# Power15V0_1A.net
KiCad netlist of a schematic drawn in Altium Designer
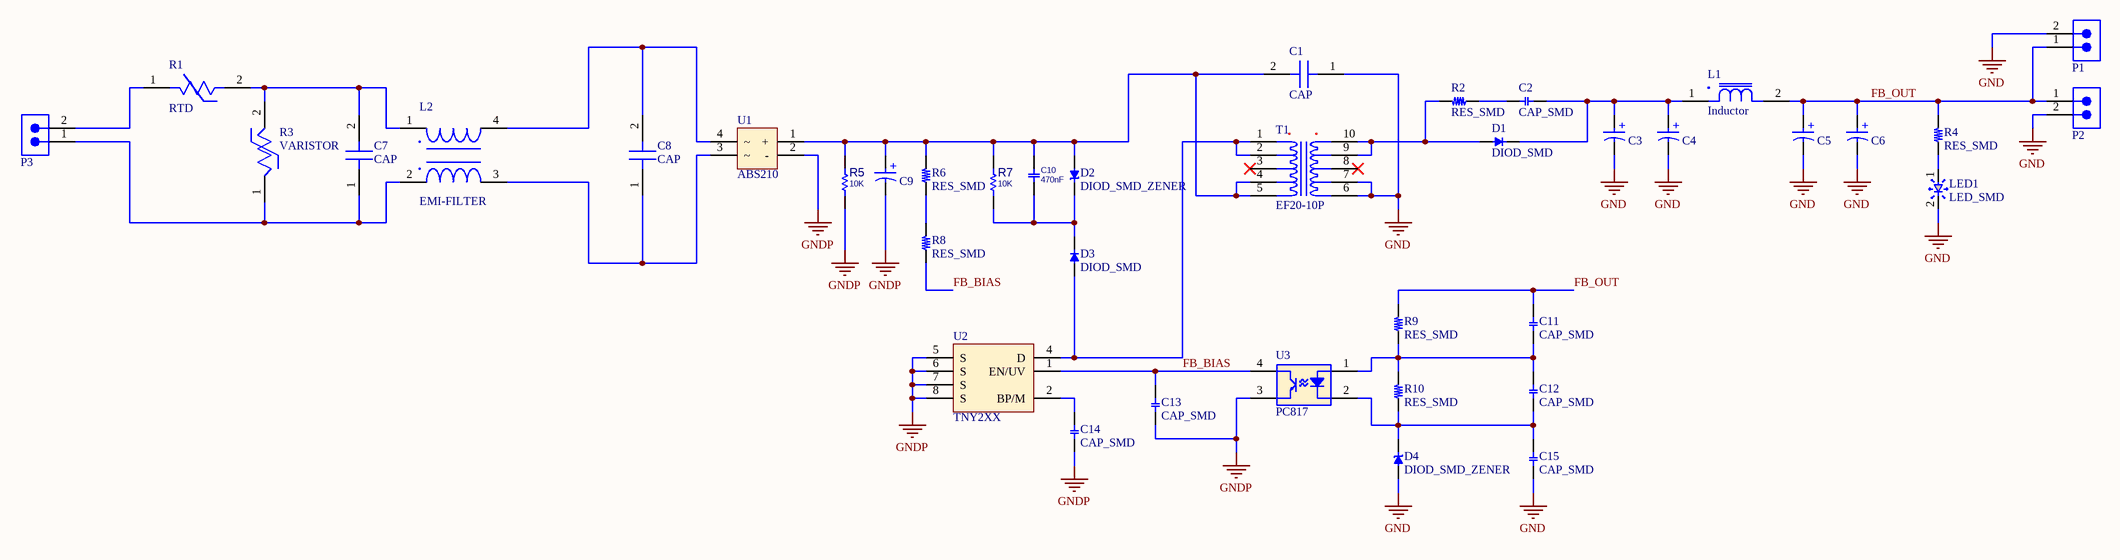
[diagram p0: Power15V0_1A.SchDoc]

(export (version "E")
  (design (tool "Eeschema 10.0.6"))
  (components
    (comp (ref "C1") (value "CAP") (footprint "CXY") (libsource (lib "radmehr_library") (part "CAP")))
    (comp (ref "C2")
      (value "CAP_SMD")
      (footprint "C 1206")
      (libsource (lib "radmehr_library") (part "CAP_SMD"))
    )
    (comp (ref "C3")
      (value "100µF")
      (footprint "WCAP-AS5H_D10H10.5")
      (description "WCAP-AS5H Aluminum Electrolytic Capacitor, V-Chip, D10 x H10.5mm, 100µF, 50V")
      (fields
        (field (name "MANUFACTURER PART NUMBER") "865230657013")
        (field (name "MANUFACTURER") "Wurth Elektronik")
      )
      (libsource (lib "Altium_WCAP-AS5H (rev22c)") (part "865230657013"))
    )
    (comp (ref "C4")
      (value "100µF")
      (footprint "WCAP-AS5H_D10H10.5")
      (description "WCAP-AS5H Aluminum Electrolytic Capacitor, V-Chip, D10 x H10.5mm, 100µF, 50V")
      (fields
        (field (name "MANUFACTURER PART NUMBER") "865230657013")
        (field (name "MANUFACTURER") "Wurth Elektronik")
      )
      (libsource (lib "Altium_WCAP-AS5H (rev22c)") (part "865230657013"))
    )
    (comp (ref "C5")
      (value "100µF")
      (footprint "WCAP-AS5H_D10H10.5")
      (description "WCAP-AS5H Aluminum Electrolytic Capacitor, V-Chip, D10 x H10.5mm, 100µF, 50V")
      (fields
        (field (name "MANUFACTURER PART NUMBER") "865230657013")
        (field (name "MANUFACTURER") "Wurth Elektronik")
      )
      (libsource (lib "Altium_WCAP-AS5H (rev22c)") (part "865230657013"))
    )
    (comp (ref "C6")
      (value "100µF")
      (footprint "WCAP-AS5H_D10H10.5")
      (description "WCAP-AS5H Aluminum Electrolytic Capacitor, V-Chip, D10 x H10.5mm, 100µF, 50V")
      (fields
        (field (name "MANUFACTURER PART NUMBER") "865230657013")
        (field (name "MANUFACTURER") "Wurth Elektronik")
      )
      (libsource (lib "Altium_WCAP-AS5H (rev22c)") (part "865230657013"))
    )
    (comp (ref "C7") (value "CAP") (footprint "CXY") (libsource (lib "radmehr_library") (part "CAP")))
    (comp (ref "C8") (value "CAP") (footprint "CXY") (libsource (lib "radmehr_library") (part "CAP")))
    (comp (ref "C9")
      (value "47µF")
      (footprint "WCAP-AIG8_D22H26")
      (description "WCAP-AIG8 Aluminum Electrolytic Capacitor, Snap-In, D22 x H26mm, 47µF, 450V")
      (fields
        (field (name "MANUFACTURER PART NUMBER") "861011483001")
        (field (name "MANUFACTURER") "Wurth Elektronik")
      )
      (libsource (lib "Altium_WCAP-AIG8 (rev22c)") (part "861011483001"))
    )
    (comp (ref "C10")
      (value "470nF")
      (footprint "C_PLY_6X3")
      (description "CAP, FILM,")
      (fields (field (name "MANF_P#") "MANF_PART#") (field (name "MANF") "MANF"))
      (libsource (lib "Integrated_Library_chilla") (part "CAP_THD_FILM_POLYESTER"))
    )
    (comp (ref "C11")
      (value "CAP_SMD")
      (footprint "C 1206")
      (libsource (lib "radmehr_library") (part "CAP_SMD"))
    )
    (comp (ref "C12")
      (value "CAP_SMD")
      (footprint "C 1206")
      (libsource (lib "radmehr_library") (part "CAP_SMD"))
    )
    (comp (ref "C13")
      (value "CAP_SMD")
      (footprint "C 1206")
      (libsource (lib "radmehr_library") (part "CAP_SMD"))
    )
    (comp (ref "C14")
      (value "CAP_SMD")
      (footprint "C 1206")
      (libsource (lib "radmehr_library") (part "CAP_SMD"))
    )
    (comp (ref "C15")
      (value "CAP_SMD")
      (footprint "C 1206")
      (libsource (lib "radmehr_library") (part "CAP_SMD"))
    )
    (comp (ref "D1")
      (value "DIOD_SMD")
      (footprint "DIOD_SMC")
      (libsource (lib "radmehr_library") (part "DIOD_SMD"))
    )
    (comp (ref "D2")
      (value "DIOD_SMD_ZENER")
      (footprint "DIOD_SMB")
      (libsource (lib "radmehr_library") (part "DIOD_SMD_ZENER"))
    )
    (comp (ref "D3")
      (value "DIOD_SMD")
      (footprint "DIOD_SMB")
      (libsource (lib "radmehr_library") (part "DIOD_SMD"))
    )
    (comp (ref "D4")
      (value "DIOD_SMD_ZENER")
      (footprint "DIOD_SMA")
      (libsource (lib "radmehr_library") (part "DIOD_SMD_ZENER"))
    )
    (comp (ref "L1")
      (value "Inductor")
      (footprint "L_12*12_SMD")
      (libsource (lib "radmehr_library") (part "Inductor"))
    )
    (comp (ref "L2")
      (value "EMI-FILTER")
      (footprint "EMI-FILTER-10*13")
      (libsource (lib "radmehr_library") (part "EMI-FILTER"))
    )
    (comp (ref "LED1")
      (value "LED_SMD")
      (footprint "D 1206")
      (libsource (lib "radmehr_library") (part "LED_SMD"))
    )
    (comp (ref "P1")
      (value "691322310002")
      (footprint "691322310002")
      (description "WR-TBL Series 322 Horizontal PCB Header, Through Hole, pitch 3.81mm, 2p")
      (fields (field (name "MANUFACTURER") "Wurth Elektronik"))
      (libsource (lib "Altium_WR-TBL (rev22a)") (part "691322310002"))
    )
    (comp (ref "P2")
      (value "691322310002")
      (footprint "691322310002")
      (description "WR-TBL Series 322 Horizontal PCB Header, Through Hole, pitch 3.81mm, 2p")
      (fields (field (name "MANUFACTURER") "Wurth Elektronik"))
      (libsource (lib "Altium_WR-TBL (rev22a)") (part "691322310002"))
    )
    (comp (ref "P3")
      (value "691322310002")
      (footprint "691322310002")
      (description "WR-TBL Series 322 Horizontal PCB Header, Through Hole, pitch 3.81mm, 2p")
      (fields (field (name "MANUFACTURER") "Wurth Elektronik"))
      (libsource (lib "Altium_WR-TBL (rev22a)") (part "691322310002"))
    )
    (comp (ref "R1") (value "RTD") (footprint "RTD") (libsource (lib "radmehr_library") (part "RTD")))
    (comp (ref "R2")
      (value "RES_SMD")
      (footprint "R 1206")
      (libsource (lib "radmehr_library") (part "RES_SMD"))
    )
    (comp (ref "R3")
      (value "VARISTOR")
      (footprint "RTD")
      (libsource (lib "radmehr_library") (part "VARISTOR"))
    )
    (comp (ref "R4")
      (value "RES_SMD")
      (footprint "R 1206")
      (libsource (lib "radmehr_library") (part "RES_SMD"))
    )
    (comp (ref "R5")
      (value "10K")
      (footprint "R025W_AX04")
      (description "RESISTOR, THD")
      (fields (field (name "MANF_P#") "RK73H1ETTP4701F") (field (name "MANF") "KOA SPEER"))
      (libsource (lib "Integrated_Library_chilla") (part "RES_THD"))
    )
    (comp (ref "R6")
      (value "RES_SMD")
      (footprint "R 1206")
      (libsource (lib "radmehr_library") (part "RES_SMD"))
    )
    (comp (ref "R7")
      (value "10K")
      (footprint "R2W_AX_VER")
      (description "RESISTOR, THD")
      (fields (field (name "MANF_P#") "RK73H1ETTP4701F") (field (name "MANF") "KOA SPEER"))
      (libsource (lib "Integrated_Library_chilla") (part "RES_THD"))
    )
    (comp (ref "R8")
      (value "RES_SMD")
      (footprint "R 1206")
      (libsource (lib "radmehr_library") (part "RES_SMD"))
    )
    (comp (ref "R9")
      (value "RES_SMD")
      (footprint "R 1206")
      (libsource (lib "radmehr_library") (part "RES_SMD"))
    )
    (comp (ref "R10")
      (value "RES_SMD")
      (footprint "R 1206")
      (libsource (lib "radmehr_library") (part "RES_SMD"))
    )
    (comp (ref "T1")
      (value "EF20-10P")
      (footprint "EF20-10P")
      (libsource (lib "radmehr_library") (part "EF20-10P"))
    )
    (comp (ref "U1") (value "ABS210") (footprint "ABS-4") (libsource (lib "radmehr_library") (part "ABS210")))
    (comp (ref "U2")
      (value "TNY2XX")
      (footprint "PDIP-8C")
      (description "P Package (DIP-8C)\r\nG Package (SMD-8C)")
      (libsource (lib "radmehr_library") (part "TNY2XX"))
    )
    (comp (ref "U3") (value "PC817") (footprint "PSMD-4") (libsource (lib "radmehr_library") (part "PC817")))
  )
  (nets
    (net (code "1") (name "/FB_BIAS") (class "Default")
      (node (ref "C13") (pin "2") (pinfunction "2_2") (pintype "passive"))
      (node (ref "R8") (pin "1") (pinfunction "1_1") (pintype "passive"))
      (node (ref "U2") (pin "1") (pinfunction "EN/UV_1") (pintype "power_in"))
      (node (ref "U3") (pin "4") (pinfunction "C_4") (pintype "passive"))
    )
    (net (code "2") (name "/FB_OUT") (class "Default")
      (node (ref "C11") (pin "1") (pinfunction "1_1") (pintype "passive"))
      (node (ref "C5") (pin "1") (pinfunction "P_1") (pintype "passive"))
      (node (ref "C6") (pin "1") (pinfunction "P_1") (pintype "passive"))
      (node (ref "L1") (pin "2") (pintype "passive"))
      (node (ref "P1") (pin "1") (pinfunction "1_1") (pintype "passive"))
      (node (ref "P2") (pin "1") (pinfunction "1_1") (pintype "passive"))
      (node (ref "R4") (pin "2") (pinfunction "2_2") (pintype "passive"))
      (node (ref "R9") (pin "2") (pinfunction "2_2") (pintype "passive"))
    )
    (net (code "3") (name "GND") (class "Default")
      (node (ref "C1") (pin "1") (pintype "passive"))
      (node (ref "C15") (pin "2") (pinfunction "2_2") (pintype "passive"))
      (node (ref "C3") (pin "2") (pinfunction "N_2") (pintype "passive"))
      (node (ref "C4") (pin "2") (pinfunction "N_2") (pintype "passive"))
      (node (ref "C5") (pin "2") (pinfunction "N_2") (pintype "passive"))
      (node (ref "C6") (pin "2") (pinfunction "N_2") (pintype "passive"))
      (node (ref "D4") (pin "1") (pinfunction "1_1") (pintype "passive"))
      (node (ref "LED1") (pin "2") (pintype "passive"))
      (node (ref "P1") (pin "2") (pinfunction "2_2") (pintype "passive"))
      (node (ref "P2") (pin "2") (pinfunction "2_2") (pintype "passive"))
      (node (ref "T1") (pin "6") (pinfunction "6_6") (pintype "power_in"))
      (node (ref "T1") (pin "7") (pinfunction "7_7") (pintype "power_in"))
    )
    (net (code "4") (name "GNDP") (class "Default")
      (node (ref "C13") (pin "1") (pinfunction "1_1") (pintype "passive"))
      (node (ref "C14") (pin "1") (pinfunction "1_1") (pintype "passive"))
      (node (ref "C9") (pin "2") (pinfunction "N_2") (pintype "passive"))
      (node (ref "R5") (pin "1") (pinfunction "1_1") (pintype "passive"))
      (node (ref "U1") (pin "2") (pinfunction "-_2") (pintype "power_in"))
      (node (ref "U2") (pin "5") (pinfunction "S_5") (pintype "power_in"))
      (node (ref "U2") (pin "6") (pinfunction "S_6") (pintype "power_in"))
      (node (ref "U2") (pin "7") (pinfunction "S_7") (pintype "power_in"))
      (node (ref "U2") (pin "8") (pinfunction "S_8") (pintype "power_in"))
      (node (ref "U3") (pin "3") (pinfunction "E_3") (pintype "passive"))
    )
    (net (code "5") (name "Net-(C2-Pad2)") (class "Default")
      (node (ref "C2") (pin "2") (pinfunction "2_2") (pintype "passive"))
      (node (ref "R2") (pin "1") (pinfunction "1_1") (pintype "passive"))
    )
    (net (code "6") (name "Net-(C3-P)") (class "Default")
      (node (ref "C2") (pin "1") (pinfunction "1_1") (pintype "passive"))
      (node (ref "C3") (pin "1") (pinfunction "P_1") (pintype "passive"))
      (node (ref "C4") (pin "1") (pinfunction "P_1") (pintype "passive"))
      (node (ref "D1") (pin "2") (pinfunction "2_2") (pintype "passive"))
      (node (ref "L1") (pin "1") (pintype "passive"))
    )
    (net (code "7") (name "Net-(C7-Pad1)") (class "Default")
      (node (ref "C7") (pin "1") (pintype "passive"))
      (node (ref "L2") (pin "2") (pinfunction "2_2") (pintype "power_in"))
      (node (ref "P3") (pin "1") (pinfunction "1_1") (pintype "passive"))
      (node (ref "R3") (pin "1") (pinfunction "1_1") (pintype "power_in"))
    )
    (net (code "8") (name "Net-(C7-Pad2)") (class "Default")
      (node (ref "C7") (pin "2") (pintype "passive"))
      (node (ref "L2") (pin "1") (pinfunction "1_1") (pintype "power_in"))
      (node (ref "R1") (pin "2") (pinfunction "2_2") (pintype "power_in"))
      (node (ref "R3") (pin "2") (pinfunction "2_2") (pintype "power_in"))
    )
    (net (code "9") (name "Net-(C8-Pad1)") (class "Default")
      (node (ref "C8") (pin "1") (pintype "passive"))
      (node (ref "L2") (pin "3") (pinfunction "3_3") (pintype "power_in"))
      (node (ref "U1") (pin "3") (pinfunction "~_3") (pintype "power_in"))
    )
    (net (code "10") (name "Net-(C8-Pad2)") (class "Default")
      (node (ref "C8") (pin "2") (pintype "passive"))
      (node (ref "L2") (pin "4") (pinfunction "4_4") (pintype "power_in"))
      (node (ref "U1") (pin "4") (pinfunction "~_4") (pintype "power_in"))
    )
    (net (code "11") (name "Net-(C9-P)") (class "Default")
      (node (ref "C1") (pin "2") (pintype "passive"))
      (node (ref "C10") (pin "2") (pinfunction "2_2") (pintype "passive"))
      (node (ref "C9") (pin "1") (pinfunction "P_1") (pintype "passive"))
      (node (ref "D2") (pin "1") (pinfunction "1_1") (pintype "passive"))
      (node (ref "R5") (pin "2") (pinfunction "2_2") (pintype "passive"))
      (node (ref "R6") (pin "2") (pinfunction "2_2") (pintype "passive"))
      (node (ref "R7") (pin "2") (pinfunction "2_2") (pintype "passive"))
      (node (ref "T1") (pin "4") (pinfunction "4_4") (pintype "power_in"))
      (node (ref "T1") (pin "5") (pinfunction "5_5") (pintype "power_in"))
      (node (ref "U1") (pin "1") (pinfunction "+_1") (pintype "power_in"))
    )
    (net (code "12") (name "Net-(C10-Pad1)") (class "Default")
      (node (ref "C10") (pin "1") (pinfunction "1_1") (pintype "passive"))
      (node (ref "D2") (pin "2") (pinfunction "2_2") (pintype "passive"))
      (node (ref "D3") (pin "2") (pinfunction "2_2") (pintype "passive"))
      (node (ref "R7") (pin "1") (pinfunction "1_1") (pintype "passive"))
    )
    (net (code "13") (name "Net-(C12-Pad2)") (class "Default")
      (node (ref "C12") (pin "2") (pinfunction "2_2") (pintype "passive"))
      (node (ref "C15") (pin "1") (pinfunction "1_1") (pintype "passive"))
      (node (ref "D4") (pin "2") (pinfunction "2_2") (pintype "passive"))
      (node (ref "R10") (pin "1") (pinfunction "1_1") (pintype "passive"))
      (node (ref "U3") (pin "2") (pinfunction "C_2") (pintype "passive"))
    )
    (net (code "14") (name "Net-(D1-Pad1)") (class "Default")
      (node (ref "D1") (pin "1") (pinfunction "1_1") (pintype "passive"))
      (node (ref "R2") (pin "2") (pinfunction "2_2") (pintype "passive"))
      (node (ref "T1") (pin "10") (pinfunction "10_10") (pintype "power_in"))
      (node (ref "T1") (pin "9") (pinfunction "9_9") (pintype "power_in"))
    )
    (net (code "15") (name "Net-(LED1-Pad1)") (class "Default")
      (node (ref "LED1") (pin "1") (pintype "passive"))
      (node (ref "R4") (pin "1") (pinfunction "1_1") (pintype "passive"))
    )
    (net (code "16") (name "Net-(P3-Pad2)") (class "Default")
      (node (ref "P3") (pin "2") (pinfunction "2_2") (pintype "passive"))
      (node (ref "R1") (pin "1") (pinfunction "1_1") (pintype "power_in"))
    )
    (net (code "17") (name "Net-(R6-Pad1)") (class "Default")
      (node (ref "R6") (pin "1") (pinfunction "1_1") (pintype "passive"))
      (node (ref "R8") (pin "2") (pinfunction "2_2") (pintype "passive"))
    )
    (net (code "18") (name "Net-(U2-BP{slash}M)") (class "Default")
      (node (ref "C14") (pin "2") (pinfunction "2_2") (pintype "passive"))
      (node (ref "U2") (pin "2") (pinfunction "BP/M_2") (pintype "power_in"))
    )
    (net (code "19") (name "Net-(U2-D)") (class "Default")
      (node (ref "D3") (pin "1") (pinfunction "1_1") (pintype "passive"))
      (node (ref "T1") (pin "1") (pinfunction "1_1") (pintype "power_in"))
      (node (ref "T1") (pin "2") (pinfunction "2_2") (pintype "power_in"))
      (node (ref "U2") (pin "4") (pinfunction "D_4") (pintype "power_in"))
    )
    (net (code "20") (name "Net-(U3-A)") (class "Default")
      (node (ref "C11") (pin "2") (pinfunction "2_2") (pintype "passive"))
      (node (ref "C12") (pin "1") (pinfunction "1_1") (pintype "passive"))
      (node (ref "R10") (pin "2") (pinfunction "2_2") (pintype "passive"))
      (node (ref "R9") (pin "1") (pinfunction "1_1") (pintype "passive"))
      (node (ref "U3") (pin "1") (pinfunction "A_1") (pintype "passive"))
    )
    (net (code "21") (name "unconnected-(T1-Pad3)") (class "Default")
      (node (ref "T1") (pin "3") (pinfunction "3_3") (pintype "power_in+no_connect"))
    )
    (net (code "22") (name "unconnected-(T1-Pad8)") (class "Default")
      (node (ref "T1") (pin "8") (pinfunction "8_8") (pintype "power_in+no_connect"))
    )
  )
)
